# LVDS_IFCB.net
KiCad netlist of a schematic drawn in Altium Designer
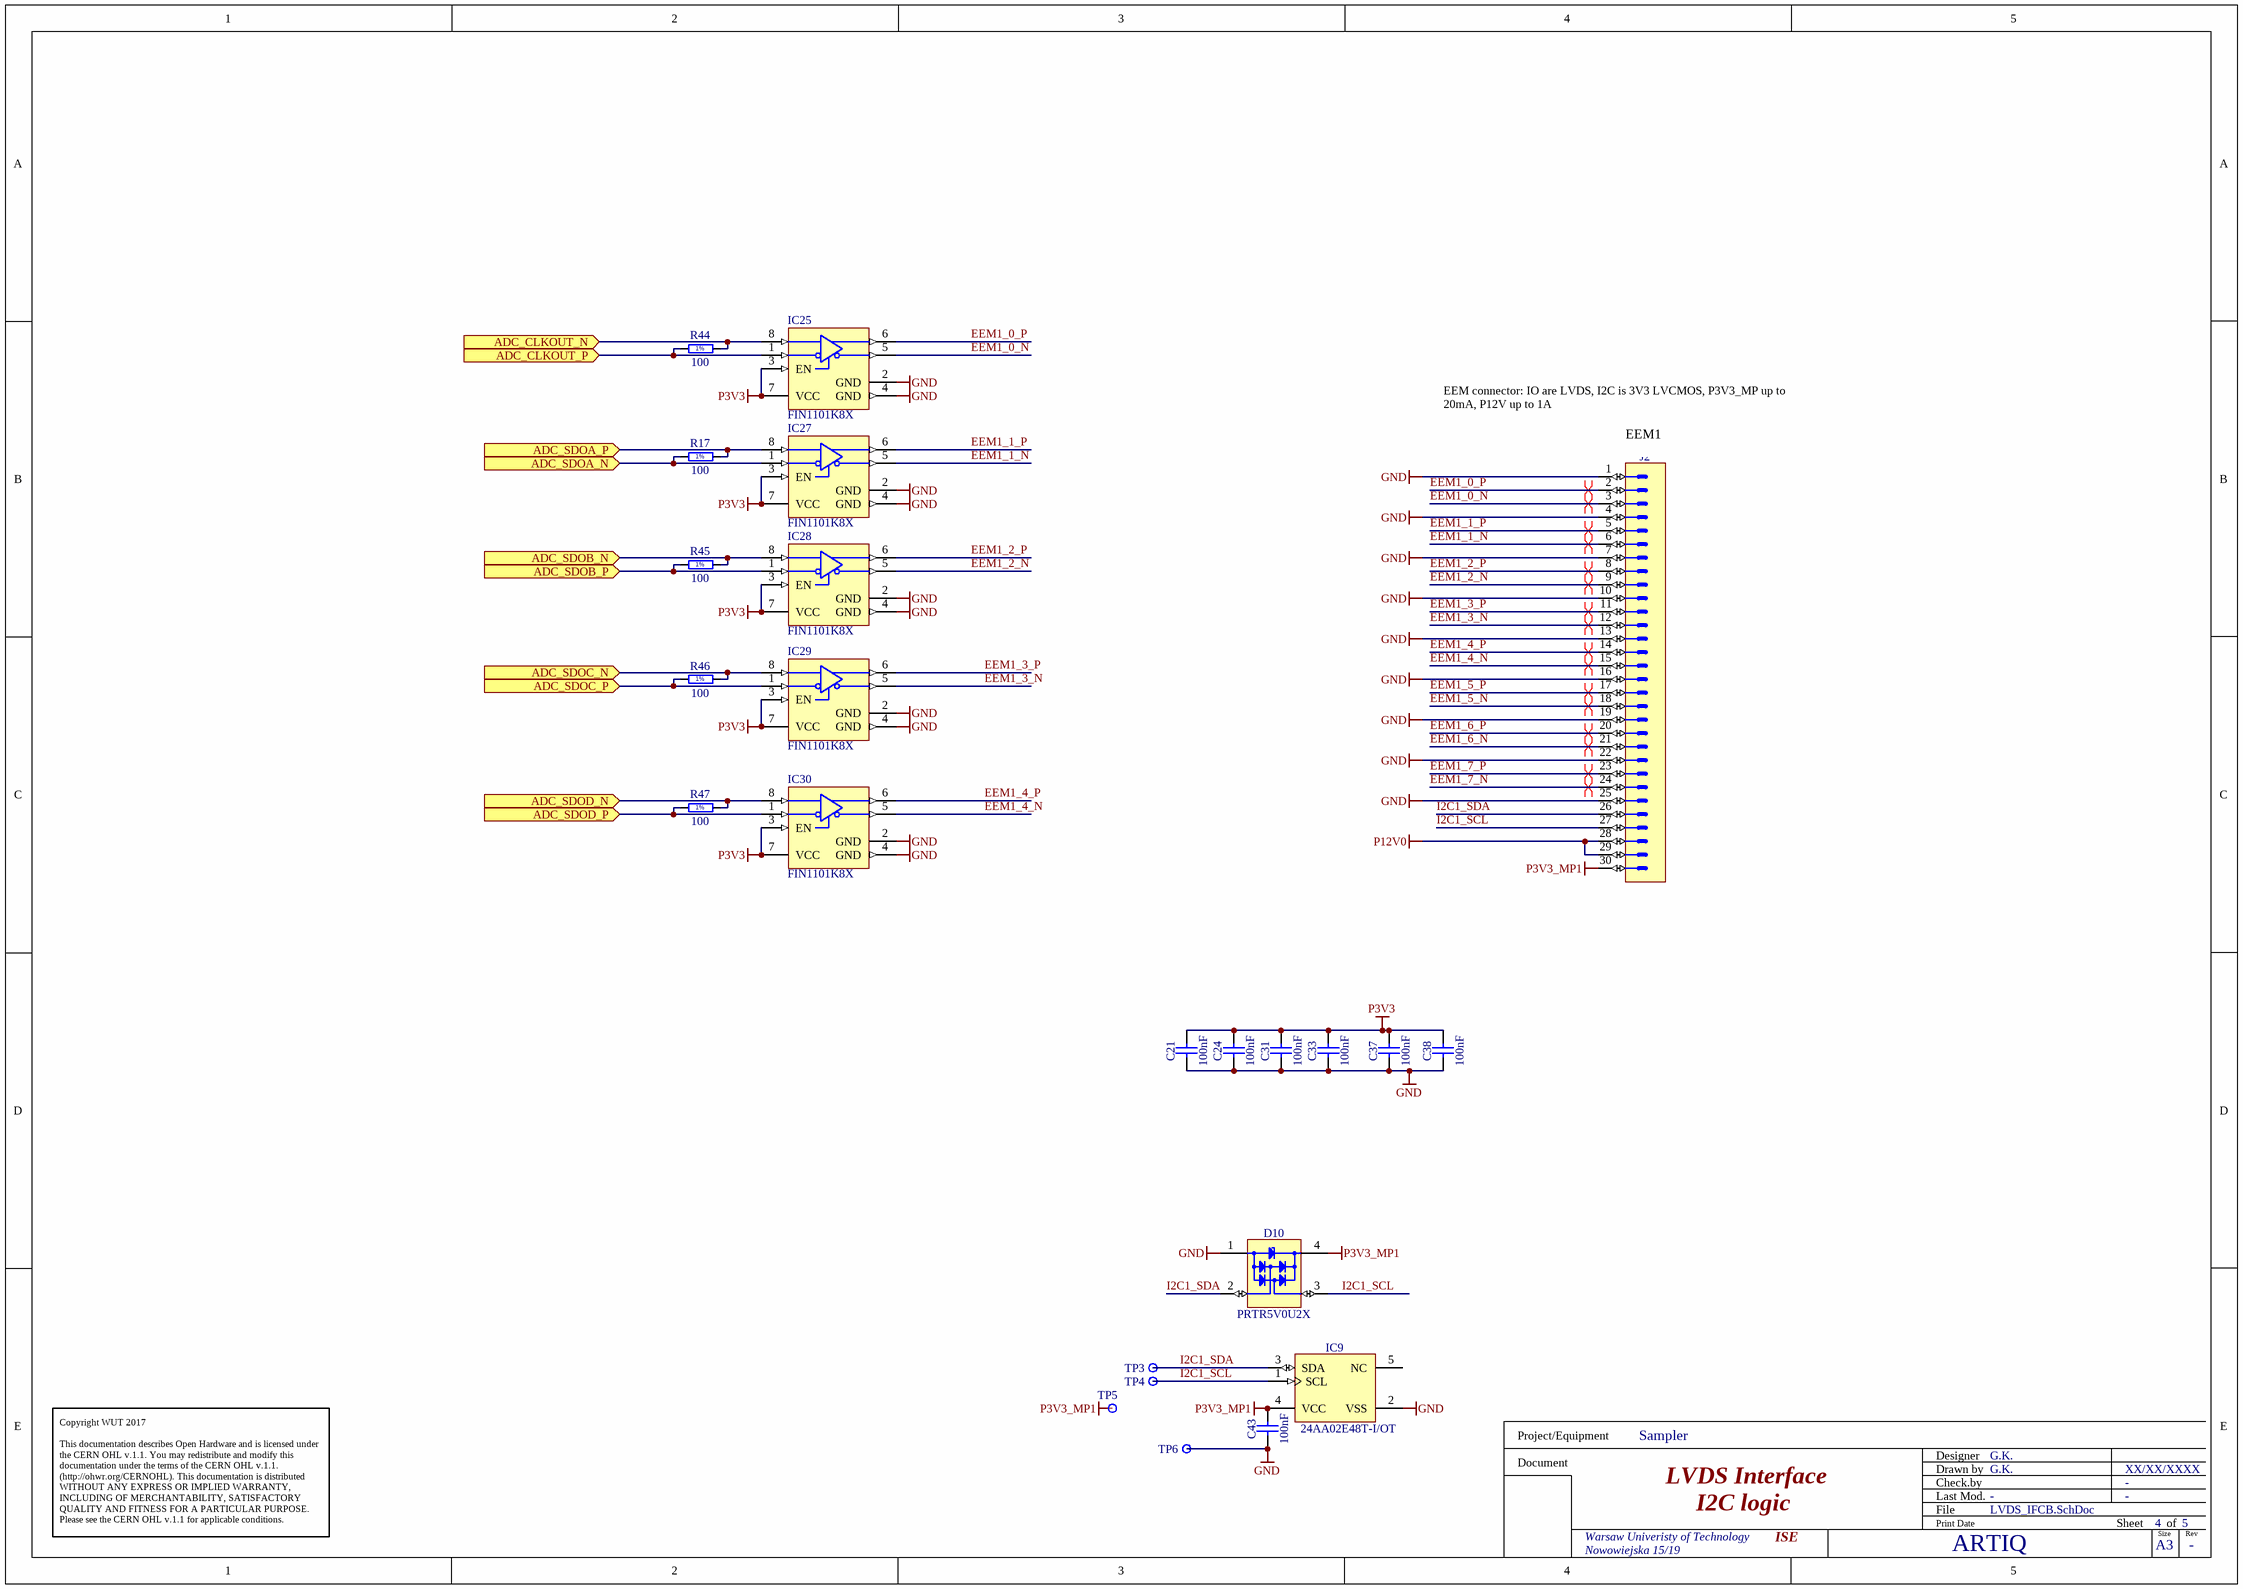
[diagram p0: LVDS_IFCB.SchDoc]

(export (version "E")
  (design (tool "Eeschema 10.0.6"))
  (components
    (comp (ref "C21")
      (value "100nF")
      (footprint "CAPC1005X55N")
      (description "Non-polarised capacitor")
      (fields
        (field (name "PART NUMBER") "CC0402_100NF_16V_10%_X5R")
        (field (name "VOLTAGE") "16V")
        (field (name "AUTHOR") "CERN DEM JLC")
      )
      (libsource (lib "Capacitors") (part "Capacitor - non polarized"))
    )
    (comp (ref "C24")
      (value "100nF")
      (footprint "CAPC1005X55N")
      (description "Non-polarised capacitor")
      (fields
        (field (name "PART NUMBER") "CC0402_100NF_16V_10%_X5R")
        (field (name "VOLTAGE") "16V")
        (field (name "AUTHOR") "CERN DEM JLC")
      )
      (libsource (lib "Capacitors") (part "Capacitor - non polarized"))
    )
    (comp (ref "C31")
      (value "100nF")
      (footprint "CAPC1005X55N")
      (description "Non-polarised capacitor")
      (fields
        (field (name "PART NUMBER") "CC0402_100NF_16V_10%_X5R")
        (field (name "VOLTAGE") "16V")
        (field (name "AUTHOR") "CERN DEM JLC")
      )
      (libsource (lib "Capacitors") (part "Capacitor - non polarized"))
    )
    (comp (ref "C33")
      (value "100nF")
      (footprint "CAPC1005X55N")
      (description "Non-polarised capacitor")
      (fields
        (field (name "PART NUMBER") "CC0402_100NF_16V_10%_X5R")
        (field (name "VOLTAGE") "16V")
        (field (name "AUTHOR") "CERN DEM JLC")
      )
      (libsource (lib "Capacitors") (part "Capacitor - non polarized"))
    )
    (comp (ref "C37")
      (value "100nF")
      (footprint "CAPC1005X55N")
      (description "Non-polarised capacitor")
      (fields
        (field (name "PART NUMBER") "CC0402_100NF_16V_10%_X5R")
        (field (name "VOLTAGE") "16V")
        (field (name "AUTHOR") "CERN DEM JLC")
      )
      (libsource (lib "Capacitors") (part "Capacitor - non polarized"))
    )
    (comp (ref "C38")
      (value "100nF")
      (footprint "CAPC1005X55N")
      (description "Non-polarised capacitor")
      (fields
        (field (name "PART NUMBER") "CC0402_100NF_16V_10%_X5R")
        (field (name "VOLTAGE") "16V")
        (field (name "AUTHOR") "CERN DEM JLC")
      )
      (libsource (lib "Capacitors") (part "Capacitor - non polarized"))
    )
    (comp (ref "C43")
      (value "100nF")
      (footprint "CAPC1005X55N")
      (description "Non-polarised capacitor")
      (fields
        (field (name "PART NUMBER") "CC0402_100NF_16V_10%_X5R")
        (field (name "VOLTAGE") "16V")
        (field (name "AUTHOR") "CERN DEM JLC")
      )
      (libsource (lib "Capacitors") (part "Capacitor - non polarized"))
    )
    (comp (ref "D10")
      (value "PRTR5V0U2X")
      (footprint "SOT190P230X110-4N")
      (description "Ultra Low Capacitance Double Rail-to-Rail ESD Protection Diode")
      (fields
        (field (name "VOLTAGE") "5.5V")
        (field (name "MANUFACTURER") "NXP SEMICONDUCTORS")
        (field (name "AUTHOR") "CERN DEM JLC")
      )
      (libsource (lib "ICs And Semiconductors") (part "PRTR5V0U2X"))
    )
    (comp (ref "IC9")
      (value "24AA02E48T-I/OT")
      (footprint "SOT95P280X145-5N")
      (description "1.7V-5.5V, 2K I2C Serial EEPROM With EUI-48 Node Identity")
      (fields (field (name "MANUFACTURER") "MICROCHIP TECHNOLOGY") (field (name "AUTHOR") "CERN DEM MR"))
      (libsource (lib "ICs And Semiconductors") (part "24AA02E48T-I/OT"))
    )
    (comp (ref "IC25")
      (value "FIN1101K8X")
      (footprint "SOP50P310X90-8N")
      (description "LVDS Single Port High Speed Repeater")
      (fields (field (name "MANUFACTURER") "FAIRCHILD SEMICONDUCTOR") (field (name "AUTHOR") "CERN DEM JLC"))
      (libsource (lib "ICs And Semiconductors") (part "FIN1101K8X"))
    )
    (comp (ref "IC27")
      (value "FIN1101K8X")
      (footprint "SOP50P310X90-8N")
      (description "LVDS Single Port High Speed Repeater")
      (fields (field (name "MANUFACTURER") "FAIRCHILD SEMICONDUCTOR") (field (name "AUTHOR") "CERN DEM JLC"))
      (libsource (lib "ICs And Semiconductors") (part "FIN1101K8X"))
    )
    (comp (ref "IC28")
      (value "FIN1101K8X")
      (footprint "SOP50P310X90-8N")
      (description "LVDS Single Port High Speed Repeater")
      (fields (field (name "MANUFACTURER") "FAIRCHILD SEMICONDUCTOR") (field (name "AUTHOR") "CERN DEM JLC"))
      (libsource (lib "ICs And Semiconductors") (part "FIN1101K8X"))
    )
    (comp (ref "IC29")
      (value "FIN1101K8X")
      (footprint "SOP50P310X90-8N")
      (description "LVDS Single Port High Speed Repeater")
      (fields (field (name "MANUFACTURER") "FAIRCHILD SEMICONDUCTOR") (field (name "AUTHOR") "CERN DEM JLC"))
      (libsource (lib "ICs And Semiconductors") (part "FIN1101K8X"))
    )
    (comp (ref "IC30")
      (value "FIN1101K8X")
      (footprint "SOP50P310X90-8N")
      (description "LVDS Single Port High Speed Repeater")
      (fields (field (name "MANUFACTURER") "FAIRCHILD SEMICONDUCTOR") (field (name "AUTHOR") "CERN DEM JLC"))
      (libsource (lib "ICs And Semiconductors") (part "FIN1101K8X"))
    )
    (comp (ref "J2")
      (value "~")
      (footprint "3M_N2530-6002RB")
      (description "Connector 30 Male")
      (fields
        (field (name "PART NUMBER") "3M_N2530-6002RB")
        (field (name "MANUFACTURER") "3M")
        (field (name "AUTHOR") "CERN DEM JLC")
      )
      (libsource (lib "Connectors") (part "Connector 30 Male"))
    )
    (comp (ref "R17")
      (value "100")
      (footprint "RESC1005X40N")
      (description "Resistor - 1%")
      (fields
        (field (name "PART NUMBER") "R0402_100R_1%_0.1W_100PPM")
        (field (name "POWER") "0.1W")
        (field (name "AUTHOR") "CERN DEM JLC")
      )
      (libsource (lib "Resistors") (part "Resistor - 1%"))
    )
    (comp (ref "R44")
      (value "100")
      (footprint "RESC1005X40N")
      (description "Resistor - 1%")
      (fields
        (field (name "PART NUMBER") "R0402_100R_1%_0.1W_100PPM")
        (field (name "POWER") "0.1W")
        (field (name "AUTHOR") "CERN DEM JLC")
      )
      (libsource (lib "Resistors") (part "Resistor - 1%"))
    )
    (comp (ref "R45")
      (value "100")
      (footprint "RESC1005X40N")
      (description "Resistor - 1%")
      (fields
        (field (name "PART NUMBER") "R0402_100R_1%_0.1W_100PPM")
        (field (name "POWER") "0.1W")
        (field (name "AUTHOR") "CERN DEM JLC")
      )
      (libsource (lib "Resistors") (part "Resistor - 1%"))
    )
    (comp (ref "R46")
      (value "100")
      (footprint "RESC1005X40N")
      (description "Resistor - 1%")
      (fields
        (field (name "PART NUMBER") "R0402_100R_1%_0.1W_100PPM")
        (field (name "POWER") "0.1W")
        (field (name "AUTHOR") "CERN DEM JLC")
      )
      (libsource (lib "Resistors") (part "Resistor - 1%"))
    )
    (comp (ref "R47")
      (value "100")
      (footprint "RESC1005X40N")
      (description "Resistor - 1%")
      (fields
        (field (name "PART NUMBER") "R0402_100R_1%_0.1W_100PPM")
        (field (name "POWER") "0.1W")
        (field (name "AUTHOR") "CERN DEM JLC")
      )
      (libsource (lib "Resistors") (part "Resistor - 1%"))
    )
    (comp (ref "TP3")
      (value "Test Point")
      (footprint "TPS127")
      (fields (field (name "PART NUMBER") "SMD_PAD_1.27X1.27MM") (field (name "AUTHOR") "CERN DEM JLC"))
      (libsource (lib "Eletro-mechanical") (part "Test Point"))
    )
    (comp (ref "TP4")
      (value "Test Point")
      (footprint "TPS127")
      (fields (field (name "PART NUMBER") "SMD_PAD_1.27X1.27MM") (field (name "AUTHOR") "CERN DEM JLC"))
      (libsource (lib "Eletro-mechanical") (part "Test Point"))
    )
    (comp (ref "TP5")
      (value "Test Point")
      (footprint "TPS127")
      (fields (field (name "PART NUMBER") "SMD_PAD_1.27X1.27MM") (field (name "AUTHOR") "CERN DEM JLC"))
      (libsource (lib "Eletro-mechanical") (part "Test Point"))
    )
    (comp (ref "TP6")
      (value "Test Point")
      (footprint "TPS127")
      (fields (field (name "PART NUMBER") "SMD_PAD_1.27X1.27MM") (field (name "AUTHOR") "CERN DEM JLC"))
      (libsource (lib "Eletro-mechanical") (part "Test Point"))
    )
  )
  (nets
    (net (code "1") (name "/ADC_CLKOUT_N") (class "Default")
      (node (ref "IC25") (pin "8") (pinfunction "RIN+_8") (pintype "input"))
      (node (ref "R44") (pin "2") (pinfunction "2_2") (pintype "passive"))
    )
    (net (code "2") (name "/ADC_CLKOUT_P") (class "Default")
      (node (ref "IC25") (pin "1") (pinfunction "RIN-_1") (pintype "input"))
      (node (ref "R44") (pin "1") (pinfunction "1_1") (pintype "passive"))
    )
    (net (code "3") (name "/ADC_SDOA_N") (class "Default")
      (node (ref "IC27") (pin "1") (pinfunction "RIN-_1") (pintype "input"))
      (node (ref "R17") (pin "1") (pinfunction "1_1") (pintype "passive"))
    )
    (net (code "4") (name "/ADC_SDOA_P") (class "Default")
      (node (ref "IC27") (pin "8") (pinfunction "RIN+_8") (pintype "input"))
      (node (ref "R17") (pin "2") (pinfunction "2_2") (pintype "passive"))
    )
    (net (code "5") (name "/ADC_SDOB_N") (class "Default")
      (node (ref "IC28") (pin "8") (pinfunction "RIN+_8") (pintype "input"))
      (node (ref "R45") (pin "2") (pinfunction "2_2") (pintype "passive"))
    )
    (net (code "6") (name "/ADC_SDOB_P") (class "Default")
      (node (ref "IC28") (pin "1") (pinfunction "RIN-_1") (pintype "input"))
      (node (ref "R45") (pin "1") (pinfunction "1_1") (pintype "passive"))
    )
    (net (code "7") (name "/ADC_SDOC_N") (class "Default")
      (node (ref "IC29") (pin "8") (pinfunction "RIN+_8") (pintype "input"))
      (node (ref "R46") (pin "2") (pinfunction "2_2") (pintype "passive"))
    )
    (net (code "8") (name "/ADC_SDOC_P") (class "Default")
      (node (ref "IC29") (pin "1") (pinfunction "RIN-_1") (pintype "input"))
      (node (ref "R46") (pin "1") (pinfunction "1_1") (pintype "passive"))
    )
    (net (code "9") (name "/ADC_SDOD_N") (class "Default")
      (node (ref "IC30") (pin "8") (pinfunction "RIN+_8") (pintype "input"))
      (node (ref "R47") (pin "2") (pinfunction "2_2") (pintype "passive"))
    )
    (net (code "10") (name "/ADC_SDOD_P") (class "Default")
      (node (ref "IC30") (pin "1") (pinfunction "RIN-_1") (pintype "input"))
      (node (ref "R47") (pin "1") (pinfunction "1_1") (pintype "passive"))
    )
    (net (code "11") (name "/EEM1_0_N") (class "Default")
      (node (ref "IC25") (pin "5") (pinfunction "DOUT-_5") (pintype "output"))
      (node (ref "J2") (pin "3") (pinfunction "3_3") (pintype "bidirectional"))
    )
    (net (code "12") (name "/EEM1_0_P") (class "Default")
      (node (ref "IC25") (pin "6") (pinfunction "DOUT+_6") (pintype "output"))
      (node (ref "J2") (pin "2") (pinfunction "2_2") (pintype "bidirectional"))
    )
    (net (code "13") (name "/EEM1_1_N") (class "Default")
      (node (ref "IC27") (pin "5") (pinfunction "DOUT-_5") (pintype "output"))
      (node (ref "J2") (pin "6") (pinfunction "6_6") (pintype "bidirectional"))
    )
    (net (code "14") (name "/EEM1_1_P") (class "Default")
      (node (ref "IC27") (pin "6") (pinfunction "DOUT+_6") (pintype "output"))
      (node (ref "J2") (pin "5") (pinfunction "5_5") (pintype "bidirectional"))
    )
    (net (code "15") (name "/EEM1_2_N") (class "Default")
      (node (ref "IC28") (pin "5") (pinfunction "DOUT-_5") (pintype "output"))
      (node (ref "J2") (pin "9") (pinfunction "9_9") (pintype "bidirectional"))
    )
    (net (code "16") (name "/EEM1_2_P") (class "Default")
      (node (ref "IC28") (pin "6") (pinfunction "DOUT+_6") (pintype "output"))
      (node (ref "J2") (pin "8") (pinfunction "8_8") (pintype "bidirectional"))
    )
    (net (code "17") (name "/EEM1_3_N") (class "Default")
      (node (ref "IC29") (pin "5") (pinfunction "DOUT-_5") (pintype "output"))
      (node (ref "J2") (pin "12") (pinfunction "12_12") (pintype "bidirectional"))
    )
    (net (code "18") (name "/EEM1_3_P") (class "Default")
      (node (ref "IC29") (pin "6") (pinfunction "DOUT+_6") (pintype "output"))
      (node (ref "J2") (pin "11") (pinfunction "11_11") (pintype "bidirectional"))
    )
    (net (code "19") (name "/EEM1_4_N") (class "Default")
      (node (ref "IC30") (pin "5") (pinfunction "DOUT-_5") (pintype "output"))
      (node (ref "J2") (pin "15") (pinfunction "15_15") (pintype "bidirectional"))
    )
    (net (code "20") (name "/EEM1_4_P") (class "Default")
      (node (ref "IC30") (pin "6") (pinfunction "DOUT+_6") (pintype "output"))
      (node (ref "J2") (pin "14") (pinfunction "14_14") (pintype "bidirectional"))
    )
    (net (code "21") (name "/EEM1_5_N") (class "Default")
      (node (ref "J2") (pin "18") (pinfunction "18_18") (pintype "bidirectional"))
    )
    (net (code "22") (name "/EEM1_5_P") (class "Default")
      (node (ref "J2") (pin "17") (pinfunction "17_17") (pintype "bidirectional"))
    )
    (net (code "23") (name "/EEM1_6_N") (class "Default")
      (node (ref "J2") (pin "21") (pinfunction "21_21") (pintype "bidirectional"))
    )
    (net (code "24") (name "/EEM1_6_P") (class "Default")
      (node (ref "J2") (pin "20") (pinfunction "20_20") (pintype "bidirectional"))
    )
    (net (code "25") (name "/EEM1_7_N") (class "Default")
      (node (ref "J2") (pin "24") (pinfunction "24_24") (pintype "bidirectional"))
    )
    (net (code "26") (name "/EEM1_7_P") (class "Default")
      (node (ref "J2") (pin "23") (pinfunction "23_23") (pintype "bidirectional"))
    )
    (net (code "27") (name "/I2C1_SCL") (class "Default")
      (node (ref "D10") (pin "3") (pinfunction "I/O2_3") (pintype "bidirectional"))
      (node (ref "IC9") (pin "1") (pinfunction "SCL_1") (pintype "input"))
      (node (ref "J2") (pin "27") (pinfunction "27_27") (pintype "bidirectional"))
      (node (ref "TP4") (pin "1") (pinfunction "1_1") (pintype "bidirectional"))
    )
    (net (code "28") (name "/I2C1_SDA") (class "Default")
      (node (ref "D10") (pin "2") (pinfunction "I/O1_2") (pintype "bidirectional"))
      (node (ref "IC9") (pin "3") (pinfunction "SDA_3") (pintype "bidirectional"))
      (node (ref "J2") (pin "26") (pinfunction "26_26") (pintype "bidirectional"))
      (node (ref "TP3") (pin "1") (pinfunction "1_1") (pintype "bidirectional"))
    )
    (net (code "29") (name "GND") (class "Default")
      (node (ref "C21") (pin "1") (pinfunction "1_1") (pintype "passive"))
      (node (ref "C24") (pin "1") (pinfunction "1_1") (pintype "passive"))
      (node (ref "C31") (pin "1") (pinfunction "1_1") (pintype "passive"))
      (node (ref "C33") (pin "1") (pinfunction "1_1") (pintype "passive"))
      (node (ref "C37") (pin "1") (pinfunction "1_1") (pintype "passive"))
      (node (ref "C38") (pin "1") (pinfunction "1_1") (pintype "passive"))
      (node (ref "C43") (pin "1") (pinfunction "1_1") (pintype "passive"))
      (node (ref "D10") (pin "1") (pinfunction "GND_1") (pintype "power_in"))
      (node (ref "IC25") (pin "2") (pinfunction "GND_2") (pintype "power_in"))
      (node (ref "IC25") (pin "4") (pinfunction "GND_4") (pintype "output"))
      (node (ref "IC27") (pin "2") (pinfunction "GND_2") (pintype "power_in"))
      (node (ref "IC27") (pin "4") (pinfunction "GND_4") (pintype "output"))
      (node (ref "IC28") (pin "2") (pinfunction "GND_2") (pintype "power_in"))
      (node (ref "IC28") (pin "4") (pinfunction "GND_4") (pintype "output"))
      (node (ref "IC29") (pin "2") (pinfunction "GND_2") (pintype "power_in"))
      (node (ref "IC29") (pin "4") (pinfunction "GND_4") (pintype "output"))
      (node (ref "IC30") (pin "2") (pinfunction "GND_2") (pintype "power_in"))
      (node (ref "IC30") (pin "4") (pinfunction "GND_4") (pintype "output"))
      (node (ref "IC9") (pin "2") (pinfunction "VSS_2") (pintype "power_in"))
      (node (ref "J2") (pin "1") (pinfunction "1_1") (pintype "bidirectional"))
      (node (ref "J2") (pin "10") (pinfunction "10_10") (pintype "bidirectional"))
      (node (ref "J2") (pin "13") (pinfunction "13_13") (pintype "bidirectional"))
      (node (ref "J2") (pin "16") (pinfunction "16_16") (pintype "bidirectional"))
      (node (ref "J2") (pin "19") (pinfunction "19_19") (pintype "bidirectional"))
      (node (ref "J2") (pin "22") (pinfunction "22_22") (pintype "bidirectional"))
      (node (ref "J2") (pin "25") (pinfunction "25_25") (pintype "bidirectional"))
      (node (ref "J2") (pin "4") (pinfunction "4_4") (pintype "bidirectional"))
      (node (ref "J2") (pin "7") (pinfunction "7_7") (pintype "bidirectional"))
      (node (ref "TP6") (pin "1") (pinfunction "1_1") (pintype "bidirectional"))
    )
    (net (code "30") (name "P3V3") (class "Default")
      (node (ref "C21") (pin "2") (pinfunction "2_2") (pintype "passive"))
      (node (ref "C24") (pin "2") (pinfunction "2_2") (pintype "passive"))
      (node (ref "C31") (pin "2") (pinfunction "2_2") (pintype "passive"))
      (node (ref "C33") (pin "2") (pinfunction "2_2") (pintype "passive"))
      (node (ref "C37") (pin "2") (pinfunction "2_2") (pintype "passive"))
      (node (ref "C38") (pin "2") (pinfunction "2_2") (pintype "passive"))
      (node (ref "IC25") (pin "3") (pinfunction "EN_3") (pintype "input"))
      (node (ref "IC25") (pin "7") (pinfunction "VCC_7") (pintype "power_in"))
      (node (ref "IC27") (pin "3") (pinfunction "EN_3") (pintype "input"))
      (node (ref "IC27") (pin "7") (pinfunction "VCC_7") (pintype "power_in"))
      (node (ref "IC28") (pin "3") (pinfunction "EN_3") (pintype "input"))
      (node (ref "IC28") (pin "7") (pinfunction "VCC_7") (pintype "power_in"))
      (node (ref "IC29") (pin "3") (pinfunction "EN_3") (pintype "input"))
      (node (ref "IC29") (pin "7") (pinfunction "VCC_7") (pintype "power_in"))
      (node (ref "IC30") (pin "3") (pinfunction "EN_3") (pintype "input"))
      (node (ref "IC30") (pin "7") (pinfunction "VCC_7") (pintype "power_in"))
    )
    (net (code "31") (name "P3V3_MP1") (class "Default")
      (node (ref "C43") (pin "2") (pinfunction "2_2") (pintype "passive"))
      (node (ref "D10") (pin "4") (pinfunction "VCC_4") (pintype "power_in"))
      (node (ref "IC9") (pin "4") (pinfunction "VCC_4") (pintype "power_in"))
      (node (ref "J2") (pin "30") (pinfunction "30_30") (pintype "bidirectional"))
      (node (ref "TP5") (pin "1") (pinfunction "1_1") (pintype "bidirectional"))
    )
    (net (code "32") (name "P12V0") (class "Default")
      (node (ref "J2") (pin "28") (pinfunction "28_28") (pintype "bidirectional"))
      (node (ref "J2") (pin "29") (pinfunction "29_29") (pintype "bidirectional"))
    )
    (net (code "33") (name "unconnected-(IC9-NC-Pad5)") (class "Default")
      (node (ref "IC9") (pin "5") (pinfunction "NC_5") (pintype "passive"))
    )
  )
)
